# untitled.net
KiCad netlist of a schematic drawn in EAGLE
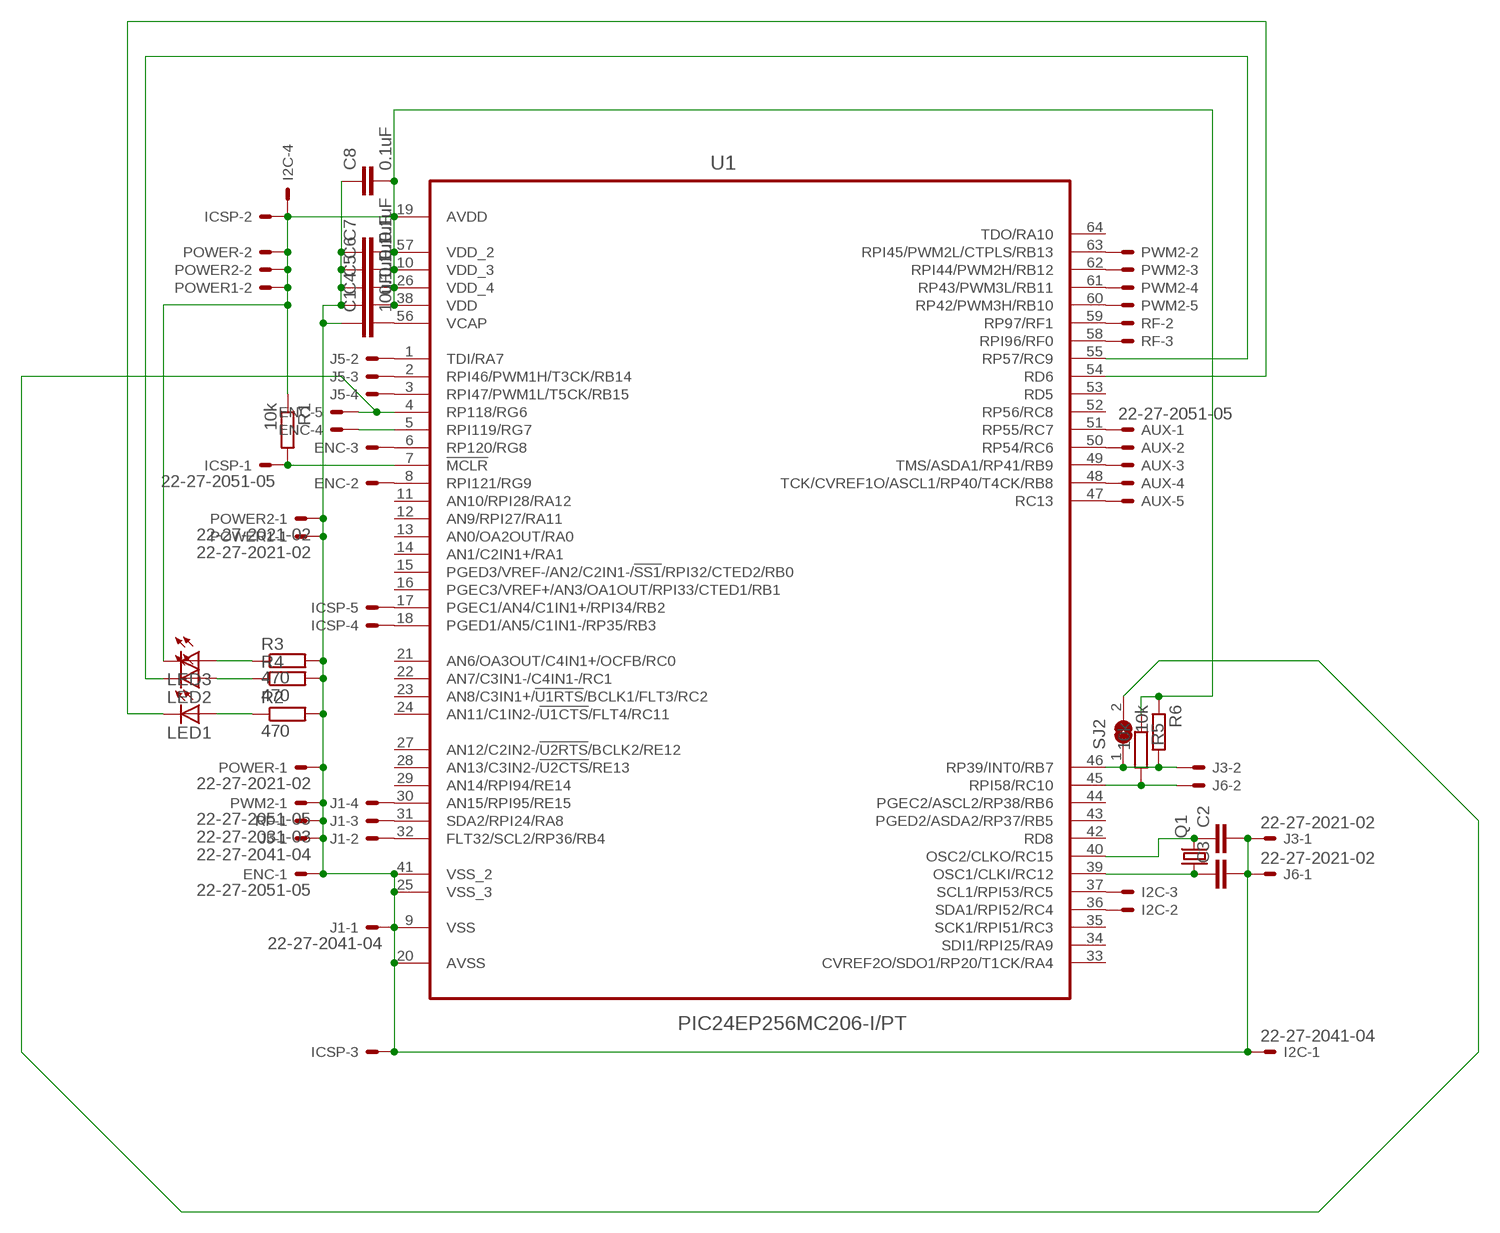
[diagram p0: schematic, sheet 1]

(export (version "E")
  (design (tool "Eeschema 10.0.6"))
  (components
    (comp (ref "AUX")
      (value "22-27-2051-05")
      (footprint "eagle-import:6410-05")
      (libsource (lib "eagle-import") (part "22-?-0527-2051"))
    )
    (comp (ref "C1")
      (value "10uF")
      (footprint "eagle-import:C0805")
      (libsource (lib "eagle-import") (part "C-EUC0805"))
    )
    (comp (ref "C2")
      (value "C-EUC0603")
      (footprint "eagle-import:C0603")
      (libsource (lib "eagle-import") (part "C-EUC0603"))
    )
    (comp (ref "C3")
      (value "C-EUC0603")
      (footprint "eagle-import:C0603")
      (libsource (lib "eagle-import") (part "C-EUC0603"))
    )
    (comp (ref "C4")
      (value "0.1uF")
      (footprint "eagle-import:C0805")
      (libsource (lib "eagle-import") (part "C-EUC0805"))
    )
    (comp (ref "C5")
      (value "0.1uF")
      (footprint "eagle-import:C0805")
      (libsource (lib "eagle-import") (part "C-EUC0805"))
    )
    (comp (ref "C6")
      (value "0.1uF")
      (footprint "eagle-import:C0805")
      (libsource (lib "eagle-import") (part "C-EUC0805"))
    )
    (comp (ref "C7")
      (value "0.1uF")
      (footprint "eagle-import:C0805")
      (libsource (lib "eagle-import") (part "C-EUC0805"))
    )
    (comp (ref "C8")
      (value "0.1uF")
      (footprint "eagle-import:C0805")
      (libsource (lib "eagle-import") (part "C-EUC0805"))
    )
    (comp (ref "ENC")
      (value "22-27-2051-05")
      (footprint "eagle-import:6410-05")
      (libsource (lib "eagle-import") (part "22-?-0527-2051"))
    )
    (comp (ref "I2C")
      (value "22-27-2041-04")
      (footprint "eagle-import:6410-04")
      (libsource (lib "eagle-import") (part "22-?-0427-2041"))
    )
    (comp (ref "ICSP")
      (value "22-27-2051-05")
      (footprint "eagle-import:6410-05")
      (libsource (lib "eagle-import") (part "22-?-0527-2051"))
    )
    (comp (ref "J1")
      (value "22-27-2041-04")
      (footprint "eagle-import:6410-04")
      (libsource (lib "eagle-import") (part "22-?-0427-2041"))
    )
    (comp (ref "J3")
      (value "22-27-2021-02")
      (footprint "eagle-import:6410-02")
      (libsource (lib "eagle-import") (part "22-?-0227-2021"))
    )
    (comp (ref "J5")
      (value "22-27-2041-04")
      (footprint "eagle-import:6410-04")
      (libsource (lib "eagle-import") (part "22-?-0427-2041"))
    )
    (comp (ref "J6")
      (value "22-27-2021-02")
      (footprint "eagle-import:6410-02")
      (libsource (lib "eagle-import") (part "22-?-0227-2021"))
    )
    (comp (ref "LED1")
      (value "LEDCHIP-LED0603")
      (footprint "eagle-import:CHIP-LED0603")
      (libsource (lib "eagle-import") (part "LEDCHIP-LED0603"))
    )
    (comp (ref "LED2")
      (value "LEDCHIP-LED0603")
      (footprint "eagle-import:CHIP-LED0603")
      (libsource (lib "eagle-import") (part "LEDCHIP-LED0603"))
    )
    (comp (ref "LED3")
      (value "LEDCHIP-LED0603")
      (footprint "eagle-import:CHIP-LED0603")
      (libsource (lib "eagle-import") (part "LEDCHIP-LED0603"))
    )
    (comp (ref "POWER")
      (value "22-27-2021-02")
      (footprint "eagle-import:6410-02")
      (libsource (lib "eagle-import") (part "22-?-0227-2021"))
    )
    (comp (ref "POWER1")
      (value "22-27-2021-02")
      (footprint "eagle-import:6410-02")
      (libsource (lib "eagle-import") (part "22-?-0227-2021"))
    )
    (comp (ref "POWER2")
      (value "22-27-2021-02")
      (footprint "eagle-import:6410-02")
      (libsource (lib "eagle-import") (part "22-?-0227-2021"))
    )
    (comp (ref "PWM2")
      (value "22-27-2051-05")
      (footprint "eagle-import:6410-05")
      (libsource (lib "eagle-import") (part "22-?-0527-2051"))
    )
    (comp (ref "Q1")
      (value "CRYSTALHC49S")
      (footprint "eagle-import:HC49_S")
      (libsource (lib "eagle-import") (part "CRYSTALHC49S"))
    )
    (comp (ref "R1")
      (value "10k")
      (footprint "eagle-import:R0805")
      (libsource (lib "eagle-import") (part "R-EU_R0805"))
    )
    (comp (ref "R2")
      (value "470")
      (footprint "eagle-import:R0805")
      (libsource (lib "eagle-import") (part "R-EU_R0805"))
    )
    (comp (ref "R3")
      (value "470")
      (footprint "eagle-import:R0805")
      (libsource (lib "eagle-import") (part "R-EU_R0805"))
    )
    (comp (ref "R4")
      (value "470")
      (footprint "eagle-import:R0805")
      (libsource (lib "eagle-import") (part "R-EU_R0805"))
    )
    (comp (ref "R5")
      (value "10k")
      (footprint "eagle-import:R0805")
      (libsource (lib "eagle-import") (part "R-EU_R0805"))
    )
    (comp (ref "R6")
      (value "10k")
      (footprint "eagle-import:R0805")
      (libsource (lib "eagle-import") (part "R-EU_R0805"))
    )
    (comp (ref "RF")
      (value "22-27-2031-03")
      (footprint "eagle-import:6410-03")
      (libsource (lib "eagle-import") (part "22-?-0327-2031"))
    )
    (comp (ref "SJ2") (value "SJ") (footprint "eagle-import:SJ") (libsource (lib "eagle-import") (part "SJ")))
    (comp (ref "U1")
      (value "PIC24EP256MC206-I/PT")
      (footprint "eagle-import:QFP50P1200X1200X120-64N")
      (libsource (lib "eagle-import") (part "PIC24EP256MC206-I/PT"))
    )
  )
  (nets
    (net (code "1") (name "Net-(AUXA-S)") (class "Default")
      (node (ref "AUX") (pin "1") (pinfunction "S_1") (pintype "passive"))
      (node (ref "U1") (pin "51") (pinfunction "RP55/RC7_51") (pintype "bidirectional"))
    )
    (net (code "2") (name "Net-(AUXB-S)") (class "Default")
      (node (ref "AUX") (pin "2") (pinfunction "S_2") (pintype "passive"))
      (node (ref "U1") (pin "50") (pinfunction "RP54/RC6_50") (pintype "bidirectional"))
    )
    (net (code "3") (name "Net-(AUXC-S)") (class "Default")
      (node (ref "AUX") (pin "3") (pinfunction "S_3") (pintype "passive"))
      (node (ref "U1") (pin "49") (pinfunction "TMS/ASDA1/RP41/RB9_49") (pintype "bidirectional"))
    )
    (net (code "4") (name "Net-(AUXD-S)") (class "Default")
      (node (ref "AUX") (pin "4") (pinfunction "S_4") (pintype "passive"))
      (node (ref "U1") (pin "48") (pinfunction "TCK/CVREF1O/ASCL1/RP40/T4CK/RB8_48") (pintype "bidirectional"))
    )
    (net (code "5") (name "Net-(AUXE-S)") (class "Default")
      (node (ref "AUX") (pin "5") (pinfunction "S_5") (pintype "passive"))
      (node (ref "U1") (pin "47") (pinfunction "RC13_47") (pintype "bidirectional"))
    )
    (net (code "6") (name "Net-(ENCA-S)") (class "Default")
      (node (ref "C1") (pin "1") (pinfunction "1_1") (pintype "passive"))
      (node (ref "C2") (pin "2") (pinfunction "2_2") (pintype "passive"))
      (node (ref "C3") (pin "2") (pinfunction "2_2") (pintype "passive"))
      (node (ref "C4") (pin "1") (pinfunction "1_1") (pintype "passive"))
      (node (ref "C5") (pin "1") (pinfunction "1_1") (pintype "passive"))
      (node (ref "C6") (pin "1") (pinfunction "1_1") (pintype "passive"))
      (node (ref "C7") (pin "1") (pinfunction "1_1") (pintype "passive"))
      (node (ref "C8") (pin "1") (pinfunction "1_1") (pintype "passive"))
      (node (ref "ENC") (pin "1") (pinfunction "S_1") (pintype "passive"))
      (node (ref "I2C") (pin "1") (pinfunction "S_1") (pintype "passive"))
      (node (ref "ICSP") (pin "3") (pinfunction "S_3") (pintype "passive"))
      (node (ref "J1") (pin "1") (pinfunction "S_1") (pintype "passive"))
      (node (ref "J3") (pin "1") (pinfunction "S_1") (pintype "passive"))
      (node (ref "J5") (pin "1") (pinfunction "S_1") (pintype "passive"))
      (node (ref "J6") (pin "1") (pinfunction "S_1") (pintype "passive"))
      (node (ref "POWER") (pin "1") (pinfunction "S_1") (pintype "passive"))
      (node (ref "POWER1") (pin "1") (pinfunction "S_1") (pintype "passive"))
      (node (ref "POWER2") (pin "1") (pinfunction "S_1") (pintype "passive"))
      (node (ref "PWM2") (pin "1") (pinfunction "S_1") (pintype "passive"))
      (node (ref "R2") (pin "2") (pinfunction "2_2") (pintype "passive"))
      (node (ref "R3") (pin "2") (pinfunction "2_2") (pintype "passive"))
      (node (ref "R4") (pin "2") (pinfunction "2_2") (pintype "passive"))
      (node (ref "RF") (pin "1") (pinfunction "S_1") (pintype "passive"))
      (node (ref "U1") (pin "20") (pinfunction "AVSS_20") (pintype "power_in"))
      (node (ref "U1") (pin "25") (pinfunction "VSS_3_25") (pintype "power_in"))
      (node (ref "U1") (pin "41") (pinfunction "VSS_2_41") (pintype "power_in"))
      (node (ref "U1") (pin "9") (pinfunction "VSS_9") (pintype "power_in"))
    )
    (net (code "7") (name "Net-(ENCB-S)") (class "Default")
      (node (ref "ENC") (pin "2") (pinfunction "S_2") (pintype "passive"))
      (node (ref "U1") (pin "8") (pinfunction "RPI121/RG9_8") (pintype "bidirectional"))
    )
    (net (code "8") (name "Net-(ENCC-S)") (class "Default")
      (node (ref "ENC") (pin "3") (pinfunction "S_3") (pintype "passive"))
      (node (ref "U1") (pin "6") (pinfunction "RP120/RG8_6") (pintype "bidirectional"))
    )
    (net (code "9") (name "Net-(ENCD-S)") (class "Default")
      (node (ref "ENC") (pin "4") (pinfunction "S_4") (pintype "passive"))
      (node (ref "U1") (pin "5") (pinfunction "RPI119/RG7_5") (pintype "bidirectional"))
    )
    (net (code "10") (name "Net-(ENCE-S)") (class "Default")
      (node (ref "ENC") (pin "5") (pinfunction "S_5") (pintype "passive"))
      (node (ref "SJ2") (pin "2") (pinfunction "2_2") (pintype "passive"))
      (node (ref "U1") (pin "4") (pinfunction "RP118/RG6_4") (pintype "bidirectional"))
    )
    (net (code "11") (name "Net-(I2CB-S)") (class "Default")
      (node (ref "I2C") (pin "2") (pinfunction "S_2") (pintype "passive"))
      (node (ref "U1") (pin "36") (pinfunction "SDA1/RPI52/RC4_36") (pintype "bidirectional"))
    )
    (net (code "12") (name "Net-(I2CC-S)") (class "Default")
      (node (ref "I2C") (pin "3") (pinfunction "S_3") (pintype "passive"))
      (node (ref "U1") (pin "37") (pinfunction "SCL1/RPI53/RC5_37") (pintype "bidirectional"))
    )
    (net (code "13") (name "Net-(I2CD-S)") (class "Default")
      (node (ref "C4") (pin "2") (pinfunction "2_2") (pintype "passive"))
      (node (ref "C5") (pin "2") (pinfunction "2_2") (pintype "passive"))
      (node (ref "C6") (pin "2") (pinfunction "2_2") (pintype "passive"))
      (node (ref "C7") (pin "2") (pinfunction "2_2") (pintype "passive"))
      (node (ref "C8") (pin "2") (pinfunction "2_2") (pintype "passive"))
      (node (ref "I2C") (pin "4") (pinfunction "S_4") (pintype "passive"))
      (node (ref "ICSP") (pin "2") (pinfunction "S_2") (pintype "passive"))
      (node (ref "LED3") (pin "C") (pinfunction "C_C") (pintype "passive"))
      (node (ref "POWER") (pin "2") (pinfunction "S_2") (pintype "passive"))
      (node (ref "POWER1") (pin "2") (pinfunction "S_2") (pintype "passive"))
      (node (ref "POWER2") (pin "2") (pinfunction "S_2") (pintype "passive"))
      (node (ref "R1") (pin "1") (pinfunction "1_1") (pintype "passive"))
      (node (ref "R5") (pin "1") (pinfunction "1_1") (pintype "passive"))
      (node (ref "R6") (pin "1") (pinfunction "1_1") (pintype "passive"))
      (node (ref "U1") (pin "10") (pinfunction "VDD_3_10") (pintype "power_in"))
      (node (ref "U1") (pin "19") (pinfunction "AVDD_19") (pintype "power_in"))
      (node (ref "U1") (pin "26") (pinfunction "VDD_4_26") (pintype "power_in"))
      (node (ref "U1") (pin "38") (pinfunction "VDD_38") (pintype "power_in"))
      (node (ref "U1") (pin "57") (pinfunction "VDD_2_57") (pintype "power_in"))
    )
    (net (code "14") (name "Net-(ICSPA-S)") (class "Default")
      (node (ref "ICSP") (pin "1") (pinfunction "S_1") (pintype "passive"))
      (node (ref "R1") (pin "2") (pinfunction "2_2") (pintype "passive"))
      (node (ref "U1") (pin "7") (pinfunction "~{MCLR}_7") (pintype "input"))
    )
    (net (code "15") (name "Net-(ICSPD-S)") (class "Default")
      (node (ref "ICSP") (pin "4") (pinfunction "S_4") (pintype "passive"))
      (node (ref "U1") (pin "18") (pinfunction "PGED1/AN5/C1IN1-/RP35/RB3_18") (pintype "bidirectional"))
    )
    (net (code "16") (name "Net-(ICSPE-S)") (class "Default")
      (node (ref "ICSP") (pin "5") (pinfunction "S_5") (pintype "passive"))
      (node (ref "U1") (pin "17") (pinfunction "PGEC1/AN4/C1IN1+/RPI34/RB2_17") (pintype "bidirectional"))
    )
    (net (code "17") (name "Net-(J1B-S)") (class "Default")
      (node (ref "J1") (pin "2") (pinfunction "S_2") (pintype "passive"))
      (node (ref "U1") (pin "32") (pinfunction "FLT32/SCL2/RP36/RB4_32") (pintype "bidirectional"))
    )
    (net (code "18") (name "Net-(J1C-S)") (class "Default")
      (node (ref "J1") (pin "3") (pinfunction "S_3") (pintype "passive"))
      (node (ref "U1") (pin "31") (pinfunction "SDA2/RPI24/RA8_31") (pintype "bidirectional"))
    )
    (net (code "19") (name "Net-(J1D-S)") (class "Default")
      (node (ref "J1") (pin "4") (pinfunction "S_4") (pintype "passive"))
      (node (ref "U1") (pin "30") (pinfunction "AN15/RPI95/RE15_30") (pintype "bidirectional"))
    )
    (net (code "20") (name "Net-(J3B-S)") (class "Default")
      (node (ref "J3") (pin "2") (pinfunction "S_2") (pintype "passive"))
      (node (ref "R6") (pin "2") (pinfunction "2_2") (pintype "passive"))
      (node (ref "SJ2") (pin "1") (pinfunction "1_1") (pintype "passive"))
      (node (ref "U1") (pin "46") (pinfunction "RP39/INT0/RB7_46") (pintype "bidirectional"))
    )
    (net (code "21") (name "Net-(J5B-S)") (class "Default")
      (node (ref "J5") (pin "2") (pinfunction "S_2") (pintype "passive"))
      (node (ref "U1") (pin "1") (pinfunction "TDI/RA7_1") (pintype "bidirectional"))
    )
    (net (code "22") (name "Net-(J5C-S)") (class "Default")
      (node (ref "J5") (pin "3") (pinfunction "S_3") (pintype "passive"))
      (node (ref "U1") (pin "2") (pinfunction "RPI46/PWM1H/T3CK/RB14_2") (pintype "bidirectional"))
    )
    (net (code "23") (name "Net-(J5D-S)") (class "Default")
      (node (ref "J5") (pin "4") (pinfunction "S_4") (pintype "passive"))
      (node (ref "U1") (pin "3") (pinfunction "RPI47/PWM1L/T5CK/RB15_3") (pintype "bidirectional"))
    )
    (net (code "24") (name "Net-(J6B-S)") (class "Default")
      (node (ref "J6") (pin "2") (pinfunction "S_2") (pintype "passive"))
      (node (ref "R5") (pin "2") (pinfunction "2_2") (pintype "passive"))
      (node (ref "U1") (pin "45") (pinfunction "RPI58/RC10_45") (pintype "bidirectional"))
    )
    (net (code "25") (name "Net-(LED1-PadA)") (class "Default")
      (node (ref "LED1") (pin "A") (pinfunction "A_A") (pintype "passive"))
      (node (ref "R2") (pin "1") (pinfunction "1_1") (pintype "passive"))
    )
    (net (code "26") (name "Net-(LED2-PadA)") (class "Default")
      (node (ref "LED2") (pin "A") (pinfunction "A_A") (pintype "passive"))
      (node (ref "R4") (pin "1") (pinfunction "1_1") (pintype "passive"))
    )
    (net (code "27") (name "Net-(LED3-PadA)") (class "Default")
      (node (ref "LED3") (pin "A") (pinfunction "A_A") (pintype "passive"))
      (node (ref "R3") (pin "1") (pinfunction "1_1") (pintype "passive"))
    )
    (net (code "28") (name "Net-(PWM2B-S)") (class "Default")
      (node (ref "PWM2") (pin "2") (pinfunction "S_2") (pintype "passive"))
      (node (ref "U1") (pin "63") (pinfunction "RPI45/PWM2L/CTPLS/RB13_63") (pintype "bidirectional"))
    )
    (net (code "29") (name "Net-(PWM2C-S)") (class "Default")
      (node (ref "PWM2") (pin "3") (pinfunction "S_3") (pintype "passive"))
      (node (ref "U1") (pin "62") (pinfunction "RPI44/PWM2H/RB12_62") (pintype "bidirectional"))
    )
    (net (code "30") (name "Net-(PWM2D-S)") (class "Default")
      (node (ref "PWM2") (pin "4") (pinfunction "S_4") (pintype "passive"))
      (node (ref "U1") (pin "61") (pinfunction "RP43/PWM3L/RB11_61") (pintype "bidirectional"))
    )
    (net (code "31") (name "Net-(PWM2E-S)") (class "Default")
      (node (ref "PWM2") (pin "5") (pinfunction "S_5") (pintype "passive"))
      (node (ref "U1") (pin "60") (pinfunction "RP42/PWM3H/RB10_60") (pintype "bidirectional"))
    )
    (net (code "32") (name "Net-(RFB-S)") (class "Default")
      (node (ref "RF") (pin "2") (pinfunction "S_2") (pintype "passive"))
      (node (ref "U1") (pin "59") (pinfunction "RP97/RF1_59") (pintype "bidirectional"))
    )
    (net (code "33") (name "Net-(RFC-S)") (class "Default")
      (node (ref "RF") (pin "3") (pinfunction "S_3") (pintype "passive"))
      (node (ref "U1") (pin "58") (pinfunction "RPI96/RF0_58") (pintype "bidirectional"))
    )
    (net (code "34") (name "Net-(U1-OSC1{slash}CLKI{slash}RC12)") (class "Default")
      (node (ref "C3") (pin "1") (pinfunction "1_1") (pintype "passive"))
      (node (ref "Q1") (pin "1") (pinfunction "1_1") (pintype "passive"))
      (node (ref "U1") (pin "39") (pinfunction "OSC1/CLKI/RC12_39") (pintype "bidirectional"))
    )
    (net (code "35") (name "Net-(U1-OSC2{slash}CLKO{slash}RC15)") (class "Default")
      (node (ref "C2") (pin "1") (pinfunction "1_1") (pintype "passive"))
      (node (ref "Q1") (pin "2") (pinfunction "2_2") (pintype "passive"))
      (node (ref "U1") (pin "40") (pinfunction "OSC2/CLKO/RC15_40") (pintype "bidirectional"))
    )
    (net (code "36") (name "Net-(U1-RD6)") (class "Default")
      (node (ref "LED1") (pin "C") (pinfunction "C_C") (pintype "passive"))
      (node (ref "U1") (pin "54") (pinfunction "RD6_54") (pintype "bidirectional"))
    )
    (net (code "37") (name "Net-(U1-RP57{slash}RC9)") (class "Default")
      (node (ref "LED2") (pin "C") (pinfunction "C_C") (pintype "passive"))
      (node (ref "U1") (pin "55") (pinfunction "RP57/RC9_55") (pintype "bidirectional"))
    )
    (net (code "38") (name "Net-(U1-VCAP)") (class "Default")
      (node (ref "C1") (pin "2") (pinfunction "2_2") (pintype "passive"))
      (node (ref "U1") (pin "56") (pinfunction "VCAP_56") (pintype "power_in"))
    )
    (net (code "39") (name "unconnected-(U1-AN0{slash}OA2OUT{slash}RA0-Pad13)") (class "Default")
      (node (ref "U1") (pin "13") (pinfunction "AN0/OA2OUT/RA0_13") (pintype "bidirectional"))
    )
    (net (code "40") (name "unconnected-(U1-AN1{slash}C2IN1+{slash}RA1-Pad14)") (class "Default")
      (node (ref "U1") (pin "14") (pinfunction "AN1/C2IN1+/RA1_14") (pintype "bidirectional"))
    )
    (net (code "41") (name "unconnected-(U1-AN6{slash}OA3OUT{slash}C4IN1+{slash}OCFB{slash}RC0-Pad21)") (class "Default")
      (node (ref "U1") (pin "21") (pinfunction "AN6/OA3OUT/C4IN1+/OCFB/RC0_21") (pintype "bidirectional"))
    )
    (net (code "42") (name "unconnected-(U1-AN7{slash}C3IN1-{slash}C4IN1-{slash}RC1-Pad22)") (class "Default")
      (node (ref "U1") (pin "22") (pinfunction "AN7/C3IN1-/C4IN1-/RC1_22") (pintype "bidirectional"))
    )
    (net (code "43") (name "unconnected-(U1-AN8{slash}C3IN1+{slash}~{U1RTS}{slash}BCLK1{slash}FLT3{slash}RC2-Pad23)") (class "Default")
      (node (ref "U1") (pin "23") (pinfunction "AN8/C3IN1+/~{U1RTS}/BCLK1/FLT3/RC2_23") (pintype "bidirectional"))
    )
    (net (code "44") (name "unconnected-(U1-AN9{slash}RPI27{slash}RA11-Pad12)") (class "Default")
      (node (ref "U1") (pin "12") (pinfunction "AN9/RPI27/RA11_12") (pintype "bidirectional"))
    )
    (net (code "45") (name "unconnected-(U1-AN10{slash}RPI28{slash}RA12-Pad11)") (class "Default")
      (node (ref "U1") (pin "11") (pinfunction "AN10/RPI28/RA12_11") (pintype "bidirectional"))
    )
    (net (code "46") (name "unconnected-(U1-AN11{slash}C1IN2-{slash}~{U1CTS}{slash}FLT4{slash}RC11-Pad24)") (class "Default")
      (node (ref "U1") (pin "24") (pinfunction "AN11/C1IN2-/~{U1CTS}/FLT4/RC11_24") (pintype "bidirectional"))
    )
    (net (code "47") (name "unconnected-(U1-AN12{slash}C2IN2-{slash}~{U2RTS}{slash}BCLK2{slash}RE12-Pad27)") (class "Default")
      (node (ref "U1") (pin "27") (pinfunction "AN12/C2IN2-/~{U2RTS}/BCLK2/RE12_27") (pintype "bidirectional"))
    )
    (net (code "48") (name "unconnected-(U1-AN13{slash}C3IN2-{slash}~{U2CTS}{slash}RE13-Pad28)") (class "Default")
      (node (ref "U1") (pin "28") (pinfunction "AN13/C3IN2-/~{U2CTS}/RE13_28") (pintype "bidirectional"))
    )
    (net (code "49") (name "unconnected-(U1-AN14{slash}RPI94{slash}RE14-Pad29)") (class "Default")
      (node (ref "U1") (pin "29") (pinfunction "AN14/RPI94/RE14_29") (pintype "bidirectional"))
    )
    (net (code "50") (name "unconnected-(U1-CVREF2O{slash}SDO1{slash}RP20{slash}T1CK{slash}RA4-Pad33)") (class "Default")
      (node (ref "U1") (pin "33") (pinfunction "CVREF2O/SDO1/RP20/T1CK/RA4_33") (pintype "bidirectional"))
    )
    (net (code "51") (name "unconnected-(U1-PGEC2{slash}ASCL2{slash}RP38{slash}RB6-Pad44)") (class "Default")
      (node (ref "U1") (pin "44") (pinfunction "PGEC2/ASCL2/RP38/RB6_44") (pintype "bidirectional"))
    )
    (net (code "52") (name "unconnected-(U1-PGEC3{slash}VREF+{slash}AN3{slash}OA1OUT{slash}RPI33{slash}CTED1{slash}RB1-Pad16)") (class "Default")
      (node (ref "U1") (pin "16") (pinfunction "PGEC3/VREF+/AN3/OA1OUT/RPI33/CTED1/RB1_16") (pintype "bidirectional"))
    )
    (net (code "53") (name "unconnected-(U1-PGED2{slash}ASDA2{slash}RP37{slash}RB5-Pad43)") (class "Default")
      (node (ref "U1") (pin "43") (pinfunction "PGED2/ASDA2/RP37/RB5_43") (pintype "bidirectional"))
    )
    (net (code "54") (name "unconnected-(U1-PGED3{slash}VREF-{slash}AN2{slash}C2IN1-{slash}~{SS1}{slash}RPI32{slash}CTED2{slash}RB0-Pad15)") (class "Default")
      (node (ref "U1") (pin "15") (pinfunction "PGED3/VREF-/AN2/C2IN1-/~{SS1}/RPI32/CTED2/RB0_15") (pintype "bidirectional"))
    )
    (net (code "55") (name "unconnected-(U1-RD5-Pad53)") (class "Default")
      (node (ref "U1") (pin "53") (pinfunction "RD5_53") (pintype "bidirectional"))
    )
    (net (code "56") (name "unconnected-(U1-RD8-Pad42)") (class "Default")
      (node (ref "U1") (pin "42") (pinfunction "RD8_42") (pintype "bidirectional"))
    )
    (net (code "57") (name "unconnected-(U1-RP56{slash}RC8-Pad52)") (class "Default")
      (node (ref "U1") (pin "52") (pinfunction "RP56/RC8_52") (pintype "bidirectional"))
    )
    (net (code "58") (name "unconnected-(U1-SCK1{slash}RPI51{slash}RC3-Pad35)") (class "Default")
      (node (ref "U1") (pin "35") (pinfunction "SCK1/RPI51/RC3_35") (pintype "bidirectional"))
    )
    (net (code "59") (name "unconnected-(U1-SDI1{slash}RPI25{slash}RA9-Pad34)") (class "Default")
      (node (ref "U1") (pin "34") (pinfunction "SDI1/RPI25/RA9_34") (pintype "bidirectional"))
    )
    (net (code "60") (name "unconnected-(U1-TDO{slash}RA10-Pad64)") (class "Default")
      (node (ref "U1") (pin "64") (pinfunction "TDO/RA10_64") (pintype "bidirectional"))
    )
  )
)
